# schema_esp01.net
KiCad netlist of a schematic drawn in EAGLE
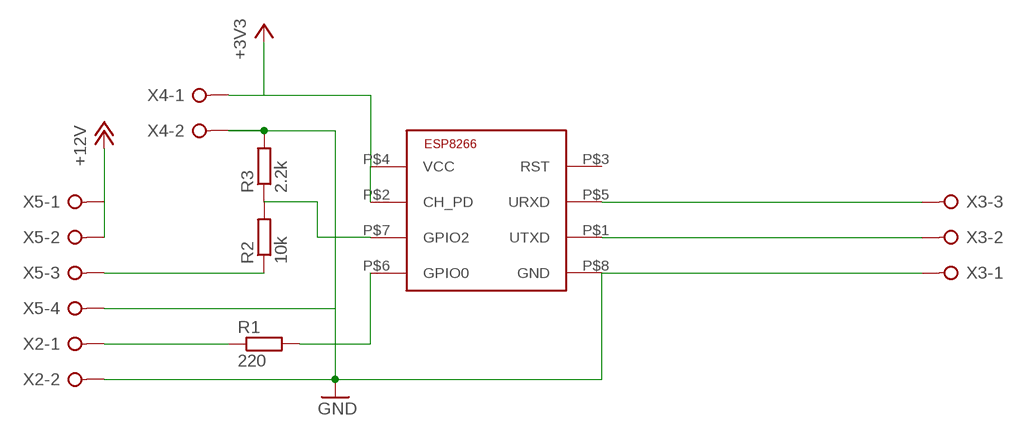
[diagram p0: schematic, sheet 1]

(export (version "E")
  (design (tool "Eeschema 10.0.6"))
  (components
    (comp (ref "R1")
      (value "220")
      (footprint "eagle-import:0204_7")
      (libsource (lib "eagle-import") (part "R-EU_0204/7"))
    )
    (comp (ref "R2")
      (value "10k")
      (footprint "eagle-import:0204_7")
      (libsource (lib "eagle-import") (part "R-EU_0204/7"))
    )
    (comp (ref "R3")
      (value "2.2k")
      (footprint "eagle-import:0204_7")
      (libsource (lib "eagle-import") (part "R-EU_0204/7"))
    )
    (comp (ref "U$1")
      (value "ESP8266-01")
      (footprint "eagle-import:ESP-01")
      (libsource (lib "eagle-import") (part "ESP8266-01"))
    )
    (comp (ref "X2")
      (value "W237-02P")
      (footprint "eagle-import:W237-132")
      (libsource (lib "eagle-import") (part "W237-02P"))
    )
    (comp (ref "X3")
      (value "W237-3E")
      (footprint "eagle-import:W237-3E")
      (libsource (lib "eagle-import") (part "W237-3E"))
    )
    (comp (ref "X4")
      (value "W237-02P")
      (footprint "eagle-import:W237-132")
      (libsource (lib "eagle-import") (part "W237-02P"))
    )
    (comp (ref "X5")
      (value "W237-04P")
      (footprint "eagle-import:W237-4P")
      (libsource (lib "eagle-import") (part "W237-04P"))
    )
  )
  (nets
    (net (code "1") (name "+3V3") (class "Default")
      (node (ref "U$1") (pin "P$2") (pinfunction "CH_PD_P$2") (pintype "bidirectional"))
      (node (ref "U$1") (pin "P$4") (pinfunction "VCC_P$4") (pintype "bidirectional"))
      (node (ref "X4") (pin "1") (pinfunction "KL_1") (pintype "passive"))
    )
    (net (code "2") (name "+12V") (class "Default")
      (node (ref "X5") (pin "1") (pinfunction "KL_1") (pintype "passive"))
      (node (ref "X5") (pin "2") (pinfunction "KL_2") (pintype "passive"))
    )
    (net (code "3") (name "GND") (class "Default")
      (node (ref "R3") (pin "2") (pinfunction "2_2") (pintype "passive"))
      (node (ref "U$1") (pin "P$8") (pinfunction "GND_P$8") (pintype "bidirectional"))
      (node (ref "X2") (pin "2") (pinfunction "KL_2") (pintype "passive"))
      (node (ref "X3") (pin "1") (pinfunction "KL_1") (pintype "passive"))
      (node (ref "X4") (pin "2") (pinfunction "KL_2") (pintype "passive"))
      (node (ref "X5") (pin "4") (pinfunction "KL_4") (pintype "passive"))
    )
    (net (code "4") (name "Net-(U$1-GPIO0)") (class "Default")
      (node (ref "R1") (pin "2") (pinfunction "2_2") (pintype "passive"))
      (node (ref "U$1") (pin "P$6") (pinfunction "GPIO0_P$6") (pintype "bidirectional"))
    )
    (net (code "5") (name "Net-(U$1-GPIO2)") (class "Default")
      (node (ref "R2") (pin "2") (pinfunction "2_2") (pintype "passive"))
      (node (ref "R3") (pin "1") (pinfunction "1_1") (pintype "passive"))
      (node (ref "U$1") (pin "P$7") (pinfunction "GPIO2_P$7") (pintype "bidirectional"))
    )
    (net (code "6") (name "Net-(U$1-URXD)") (class "Default")
      (node (ref "U$1") (pin "P$5") (pinfunction "URXD_P$5") (pintype "bidirectional"))
      (node (ref "X3") (pin "3") (pinfunction "KL_3") (pintype "passive"))
    )
    (net (code "7") (name "Net-(U$1-UTXD)") (class "Default")
      (node (ref "U$1") (pin "P$1") (pinfunction "UTXD_P$1") (pintype "bidirectional"))
      (node (ref "X3") (pin "2") (pinfunction "KL_2") (pintype "passive"))
    )
    (net (code "8") (name "Net-(X2A-KL)") (class "Default")
      (node (ref "R1") (pin "1") (pinfunction "1_1") (pintype "passive"))
      (node (ref "X2") (pin "1") (pinfunction "KL_1") (pintype "passive"))
    )
    (net (code "9") (name "Net-(X5C-KL)") (class "Default")
      (node (ref "R2") (pin "1") (pinfunction "1_1") (pintype "passive"))
      (node (ref "X5") (pin "3") (pinfunction "KL_3") (pintype "passive"))
    )
    (net (code "10") (name "unconnected-(U$1-RST-PadP$3)") (class "Default")
      (node (ref "U$1") (pin "P$3") (pinfunction "RST_P$3") (pintype "bidirectional"))
    )
  )
)
